# pagerv2.net
KiCad netlist of a schematic drawn in Altium Designer
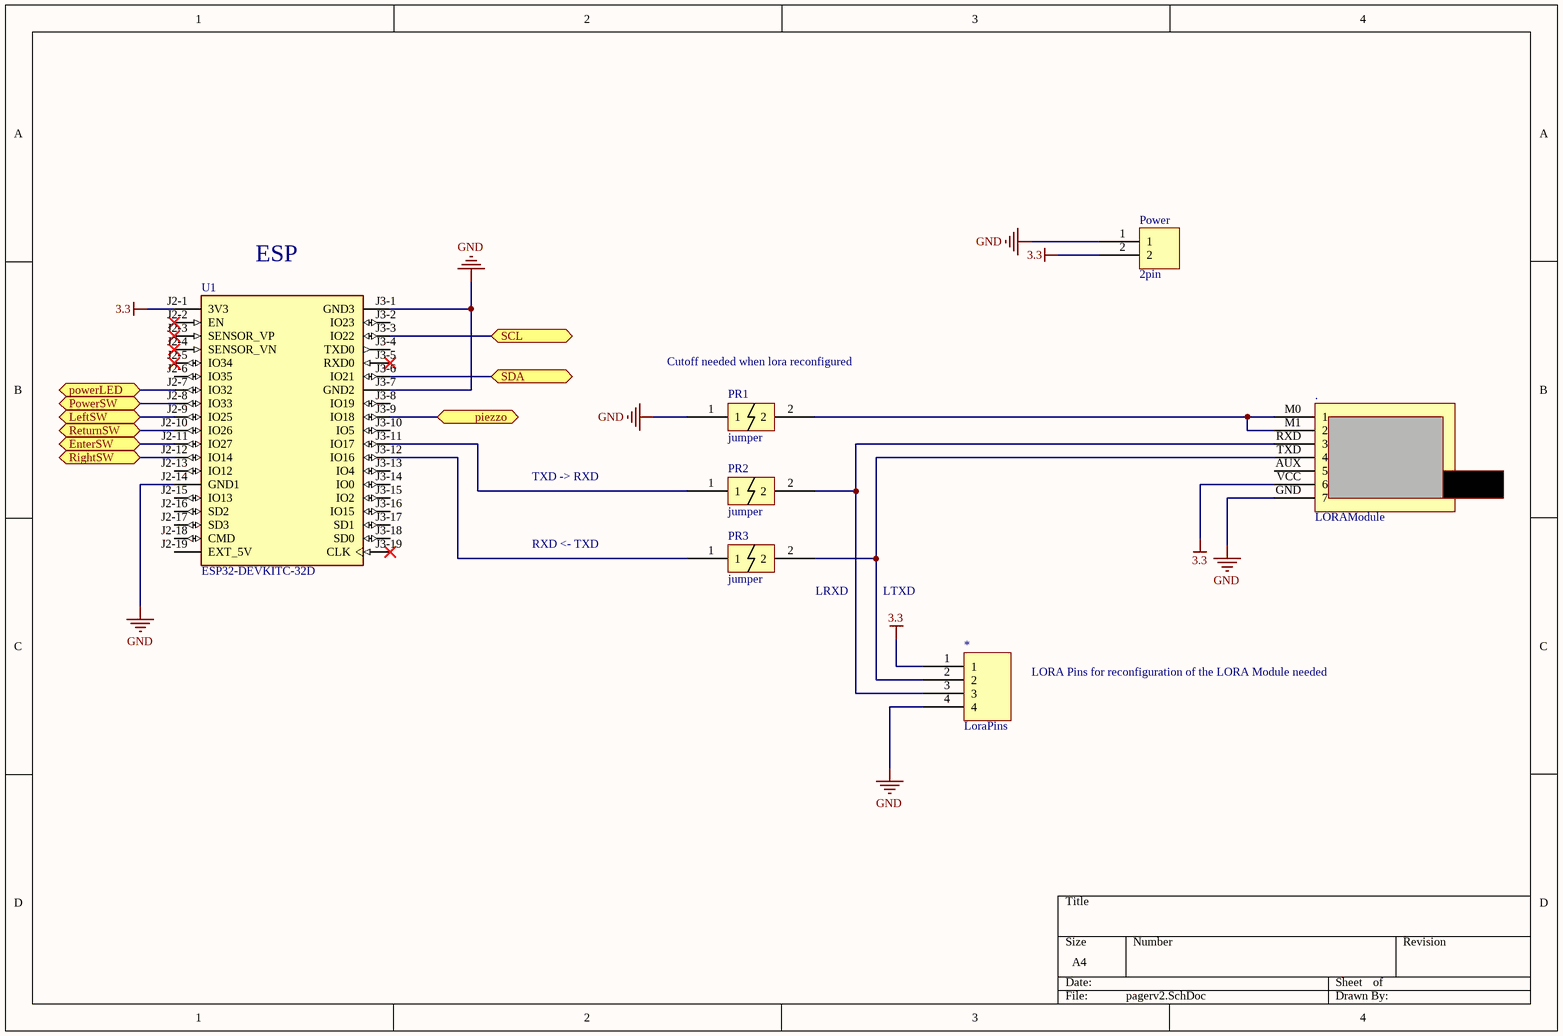
[diagram p0: pagerv2.SchDoc]

(export (version "E")
  (design (tool "Eeschema 10.0.6"))
  (components
    (comp (ref "*") (value "LoraPins") (footprint "4pin") (libsource (lib "lora") (part "LoraPins")))
    (comp (ref ".")
      (value "LORAModule")
      (footprint "LORAmodule")
      (libsource (lib "lora") (part "LORAModule"))
    )
    (comp (ref "Power") (value "2pin") (footprint "2PIN") (libsource (lib "lora") (part "2pin")))
    (comp (ref "PR1") (value "jumper") (footprint "jumper") (libsource (lib "lora") (part "jumper")))
    (comp (ref "PR2") (value "jumper") (footprint "jumper") (libsource (lib "lora") (part "jumper")))
    (comp (ref "PR3") (value "jumper") (footprint "jumper") (libsource (lib "lora") (part "jumper")))
    (comp (ref "U1")
      (value "ESP32-DEVKITC-32D")
      (footprint "MODULE_ESP32-DEVKITC-32D")
      (description "WiFi Development Tools (802.11) ESP32 General Development Kit, ESP32-WROOM-32D on the board")
      (fields (field (name "MF") "Espressif Systems"))
      (libsource (lib "bastis workspace") (part "ESP32-DEVKITC-32D"))
    )
  )
  (nets
    (net (code "1") (name "/EnterSW") (class "Default")
      (node (ref "U1") (pin "J2-11") (pinfunction "IO27_J2-11") (pintype "bidirectional"))
    )
    (net (code "2") (name "/LeftSW") (class "Default")
      (node (ref "U1") (pin "J2-9") (pinfunction "IO25_J2-9") (pintype "bidirectional"))
    )
    (net (code "3") (name "/PowerSW") (class "Default")
      (node (ref "U1") (pin "J2-8") (pinfunction "IO33_J2-8") (pintype "bidirectional"))
    )
    (net (code "4") (name "/ReturnSW") (class "Default")
      (node (ref "U1") (pin "J2-10") (pinfunction "IO26_J2-10") (pintype "bidirectional"))
    )
    (net (code "5") (name "/RightSW") (class "Default")
      (node (ref "U1") (pin "J2-12") (pinfunction "IO14_J2-12") (pintype "bidirectional"))
    )
    (net (code "6") (name "/SCL") (class "Default")
      (node (ref "U1") (pin "J3-3") (pinfunction "IO22_J3-3") (pintype "bidirectional"))
    )
    (net (code "7") (name "/SDA") (class "Default")
      (node (ref "U1") (pin "J3-6") (pinfunction "IO21_J3-6") (pintype "bidirectional"))
    )
    (net (code "8") (name "/piezzo") (class "Default")
      (node (ref "U1") (pin "J3-9") (pinfunction "IO18_J3-9") (pintype "bidirectional"))
    )
    (net (code "9") (name "/powerLED") (class "Default")
      (node (ref "U1") (pin "J2-7") (pinfunction "IO32_J2-7") (pintype "bidirectional"))
    )
    (net (code "10") (name "3.3") (class "Default")
      (node (ref "*") (pin "1") (pinfunction "1_1") (pintype "passive"))
      (node (ref ".") (pin "VCC") (pinfunction "6_VCC") (pintype "passive"))
      (node (ref "Power") (pin "2") (pinfunction "2_2") (pintype "passive"))
      (node (ref "U1") (pin "J2-1") (pinfunction "3V3_J2-1") (pintype "power_in"))
    )
    (net (code "11") (name "GND") (class "Default")
      (node (ref "*") (pin "4") (pinfunction "4_4") (pintype "passive"))
      (node (ref ".") (pin "GND") (pinfunction "7_GND") (pintype "passive"))
      (node (ref "PR1") (pin "1") (pinfunction "1_1") (pintype "passive"))
      (node (ref "Power") (pin "1") (pinfunction "1_1") (pintype "passive"))
      (node (ref "U1") (pin "J2-14") (pinfunction "GND1_J2-14") (pintype "power_in"))
      (node (ref "U1") (pin "J3-1") (pinfunction "GND3_J3-1") (pintype "power_in"))
      (node (ref "U1") (pin "J3-7") (pinfunction "GND2_J3-7") (pintype "power_in"))
    )
    (net (code "12") (name "Net-(.-1)") (class "Default")
      (node (ref ".") (pin "M0") (pinfunction "1_M0") (pintype "passive"))
      (node (ref ".") (pin "M1") (pinfunction "2_M1") (pintype "passive"))
      (node (ref "PR1") (pin "2") (pinfunction "2_2") (pintype "passive"))
    )
    (net (code "13") (name "Net-(.-3)") (class "Default")
      (node (ref "*") (pin "3") (pinfunction "3_3") (pintype "passive"))
      (node (ref ".") (pin "RXD") (pinfunction "3_RXD") (pintype "passive"))
      (node (ref "PR2") (pin "2") (pinfunction "2_2") (pintype "passive"))
    )
    (net (code "14") (name "Net-(.-4)") (class "Default")
      (node (ref "*") (pin "2") (pinfunction "2_2") (pintype "passive"))
      (node (ref ".") (pin "TXD") (pinfunction "4_TXD") (pintype "passive"))
      (node (ref "PR3") (pin "2") (pinfunction "2_2") (pintype "passive"))
    )
    (net (code "15") (name "Net-(U1-IO16)") (class "Default")
      (node (ref "PR3") (pin "1") (pinfunction "1_1") (pintype "passive"))
      (node (ref "U1") (pin "J3-12") (pinfunction "IO16_J3-12") (pintype "bidirectional"))
    )
    (net (code "16") (name "Net-(U1-IO17)") (class "Default")
      (node (ref "PR2") (pin "1") (pinfunction "1_1") (pintype "passive"))
      (node (ref "U1") (pin "J3-11") (pinfunction "IO17_J3-11") (pintype "bidirectional"))
    )
    (net (code "17") (name "unconnected-(.-5-PadAUX)") (class "Default")
      (node (ref ".") (pin "AUX") (pinfunction "5_AUX") (pintype "passive"))
    )
    (net (code "18") (name "unconnected-(U1-CLK-PadJ3-19)") (class "Default")
      (node (ref "U1") (pin "J3-19") (pinfunction "CLK_J3-19") (pintype "input+no_connect"))
    )
    (net (code "19") (name "unconnected-(U1-CMD-PadJ2-18)") (class "Default")
      (node (ref "U1") (pin "J2-18") (pinfunction "CMD_J2-18") (pintype "bidirectional"))
    )
    (net (code "20") (name "unconnected-(U1-EN-PadJ2-2)") (class "Default")
      (node (ref "U1") (pin "J2-2") (pinfunction "EN_J2-2") (pintype "input+no_connect"))
    )
    (net (code "21") (name "unconnected-(U1-EXT_5V-PadJ2-19)") (class "Default")
      (node (ref "U1") (pin "J2-19") (pinfunction "EXT_5V_J2-19") (pintype "power_in"))
    )
    (net (code "22") (name "unconnected-(U1-IO0-PadJ3-14)") (class "Default")
      (node (ref "U1") (pin "J3-14") (pinfunction "IO0_J3-14") (pintype "bidirectional"))
    )
    (net (code "23") (name "unconnected-(U1-IO2-PadJ3-15)") (class "Default")
      (node (ref "U1") (pin "J3-15") (pinfunction "IO2_J3-15") (pintype "bidirectional"))
    )
    (net (code "24") (name "unconnected-(U1-IO4-PadJ3-13)") (class "Default")
      (node (ref "U1") (pin "J3-13") (pinfunction "IO4_J3-13") (pintype "bidirectional"))
    )
    (net (code "25") (name "unconnected-(U1-IO5-PadJ3-10)") (class "Default")
      (node (ref "U1") (pin "J3-10") (pinfunction "IO5_J3-10") (pintype "bidirectional"))
    )
    (net (code "26") (name "unconnected-(U1-IO12-PadJ2-13)") (class "Default")
      (node (ref "U1") (pin "J2-13") (pinfunction "IO12_J2-13") (pintype "bidirectional"))
    )
    (net (code "27") (name "unconnected-(U1-IO13-PadJ2-15)") (class "Default")
      (node (ref "U1") (pin "J2-15") (pinfunction "IO13_J2-15") (pintype "bidirectional"))
    )
    (net (code "28") (name "unconnected-(U1-IO15-PadJ3-16)") (class "Default")
      (node (ref "U1") (pin "J3-16") (pinfunction "IO15_J3-16") (pintype "bidirectional"))
    )
    (net (code "29") (name "unconnected-(U1-IO19-PadJ3-8)") (class "Default")
      (node (ref "U1") (pin "J3-8") (pinfunction "IO19_J3-8") (pintype "bidirectional"))
    )
    (net (code "30") (name "unconnected-(U1-IO23-PadJ3-2)") (class "Default")
      (node (ref "U1") (pin "J3-2") (pinfunction "IO23_J3-2") (pintype "bidirectional"))
    )
    (net (code "31") (name "unconnected-(U1-IO34-PadJ2-5)") (class "Default")
      (node (ref "U1") (pin "J2-5") (pinfunction "IO34_J2-5") (pintype "bidirectional+no_connect"))
    )
    (net (code "32") (name "unconnected-(U1-IO35-PadJ2-6)") (class "Default")
      (node (ref "U1") (pin "J2-6") (pinfunction "IO35_J2-6") (pintype "bidirectional"))
    )
    (net (code "33") (name "unconnected-(U1-RXD0-PadJ3-5)") (class "Default")
      (node (ref "U1") (pin "J3-5") (pinfunction "RXD0_J3-5") (pintype "input+no_connect"))
    )
    (net (code "34") (name "unconnected-(U1-SD0-PadJ3-18)") (class "Default")
      (node (ref "U1") (pin "J3-18") (pinfunction "SD0_J3-18") (pintype "bidirectional"))
    )
    (net (code "35") (name "unconnected-(U1-SD1-PadJ3-17)") (class "Default")
      (node (ref "U1") (pin "J3-17") (pinfunction "SD1_J3-17") (pintype "bidirectional"))
    )
    (net (code "36") (name "unconnected-(U1-SD2-PadJ2-16)") (class "Default")
      (node (ref "U1") (pin "J2-16") (pinfunction "SD2_J2-16") (pintype "bidirectional"))
    )
    (net (code "37") (name "unconnected-(U1-SD3-PadJ2-17)") (class "Default")
      (node (ref "U1") (pin "J2-17") (pinfunction "SD3_J2-17") (pintype "bidirectional"))
    )
    (net (code "38") (name "unconnected-(U1-SENSOR_VN-PadJ2-4)") (class "Default")
      (node (ref "U1") (pin "J2-4") (pinfunction "SENSOR_VN_J2-4") (pintype "input+no_connect"))
    )
    (net (code "39") (name "unconnected-(U1-SENSOR_VP-PadJ2-3)") (class "Default")
      (node (ref "U1") (pin "J2-3") (pinfunction "SENSOR_VP_J2-3") (pintype "input+no_connect"))
    )
    (net (code "40") (name "unconnected-(U1-TXD0-PadJ3-4)") (class "Default")
      (node (ref "U1") (pin "J3-4") (pinfunction "TXD0_J3-4") (pintype "output"))
    )
  )
)
